# indsensor2.net
KiCad netlist of a schematic drawn in EAGLE
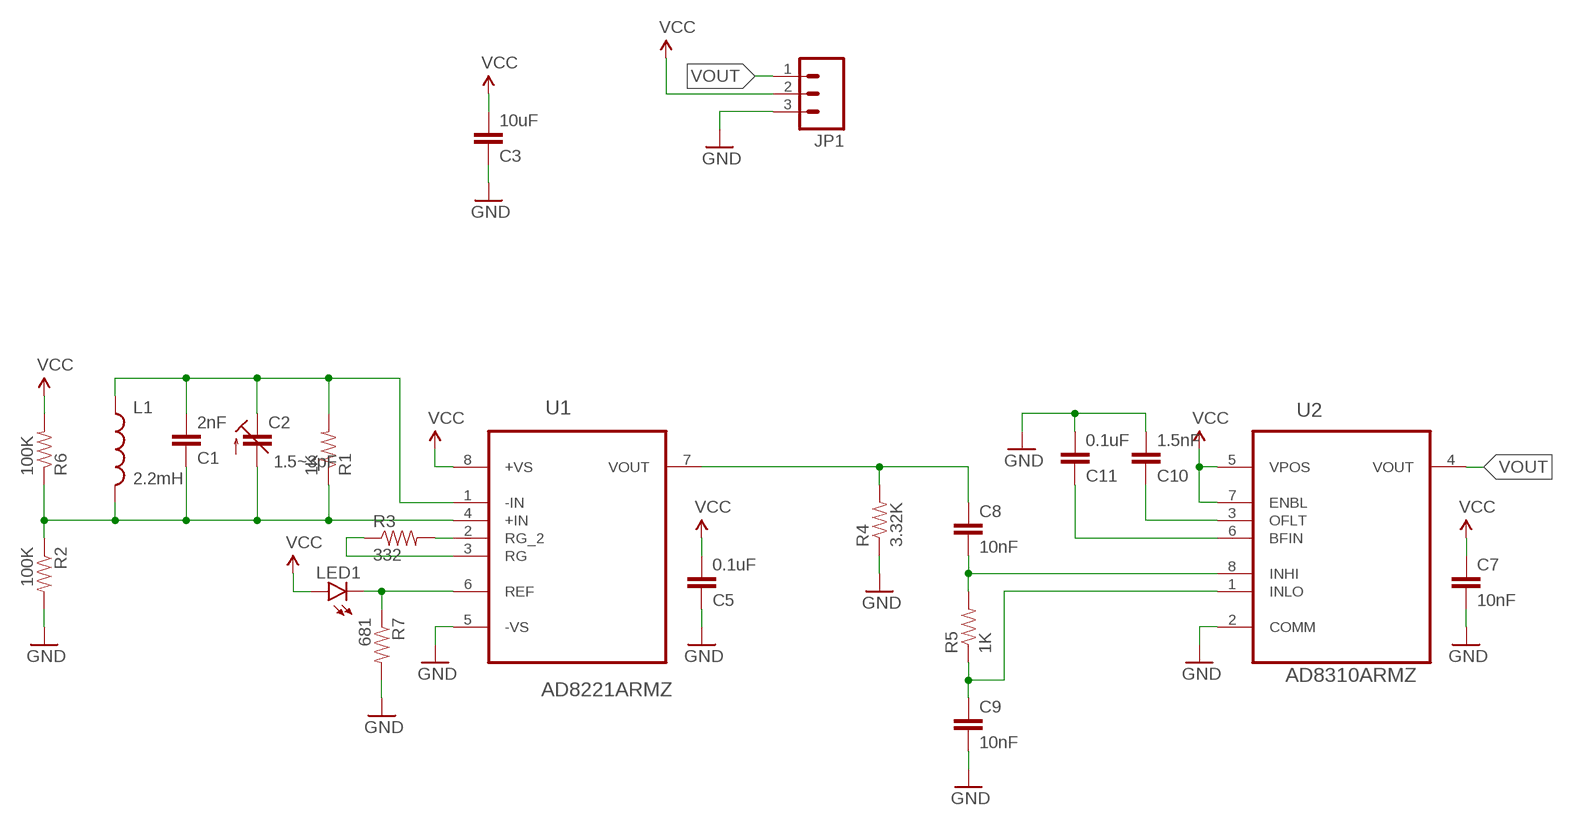
[diagram p0: schematic, sheet 1]

(export (version "E")
  (design (tool "Eeschema 10.0.6"))
  (components
    (comp (ref "C1")
      (value "2nF")
      (footprint "eagle-import:0603-CAP")
      (libsource (lib "eagle-import") (part "CAP0603-CAP"))
    )
    (comp (ref "C2")
      (value "1.5~3pF")
      (footprint "eagle-import:TRIMCAP-TZY")
      (libsource (lib "eagle-import") (part "TRIMCAP-TZY"))
    )
    (comp (ref "C3")
      (value "10uF")
      (footprint "eagle-import:0603-CAP")
      (libsource (lib "eagle-import") (part "CAP0603-CAP"))
    )
    (comp (ref "C5")
      (value "0.1uF")
      (footprint "eagle-import:0603-CAP")
      (libsource (lib "eagle-import") (part "CAP0603-CAP"))
    )
    (comp (ref "C7")
      (value "10nF")
      (footprint "eagle-import:0603-CAP")
      (libsource (lib "eagle-import") (part "CAP0603-CAP"))
    )
    (comp (ref "C8")
      (value "10nF")
      (footprint "eagle-import:0603-CAP")
      (libsource (lib "eagle-import") (part "CAP0603-CAP"))
    )
    (comp (ref "C9")
      (value "10nF")
      (footprint "eagle-import:0603-CAP")
      (libsource (lib "eagle-import") (part "CAP0603-CAP"))
    )
    (comp (ref "C10")
      (value "1.5nF")
      (footprint "eagle-import:0603-CAP")
      (libsource (lib "eagle-import") (part "CAP0603-CAP"))
    )
    (comp (ref "C11")
      (value "0.1uF")
      (footprint "eagle-import:0603-CAP")
      (libsource (lib "eagle-import") (part "CAP0603-CAP"))
    )
    (comp (ref "JP1")
      (value "M03LOCK")
      (footprint "eagle-import:1X03_LOCK")
      (libsource (lib "eagle-import") (part "M03LOCK"))
    )
    (comp (ref "L1")
      (value "2.2mH")
      (footprint "eagle-import:1812")
      (libsource (lib "eagle-import") (part "LQH43N"))
    )
    (comp (ref "LED1")
      (value "LED0603")
      (footprint "eagle-import:LED-0603")
      (libsource (lib "eagle-import") (part "LED0603"))
    )
    (comp (ref "R1")
      (value "1K")
      (footprint "eagle-import:0603-RES")
      (libsource (lib "eagle-import") (part "RESISTOR0603"))
    )
    (comp (ref "R2")
      (value "100K")
      (footprint "eagle-import:0603-RES")
      (libsource (lib "eagle-import") (part "RESISTOR0603"))
    )
    (comp (ref "R3")
      (value "332")
      (footprint "eagle-import:0603-RES")
      (libsource (lib "eagle-import") (part "RESISTOR0603"))
    )
    (comp (ref "R4")
      (value "3.32K")
      (footprint "eagle-import:0603-RES")
      (libsource (lib "eagle-import") (part "RESISTOR0603"))
    )
    (comp (ref "R5")
      (value "1K")
      (footprint "eagle-import:0603-RES")
      (libsource (lib "eagle-import") (part "RESISTOR0603"))
    )
    (comp (ref "R6")
      (value "100K")
      (footprint "eagle-import:0603-RES")
      (libsource (lib "eagle-import") (part "RESISTOR0603"))
    )
    (comp (ref "R7")
      (value "681")
      (footprint "eagle-import:0603-RES")
      (libsource (lib "eagle-import") (part "RESISTOR0603"))
    )
    (comp (ref "U1")
      (value "AD8221ARMZ")
      (footprint "eagle-import:SOP65P490X110-8N")
      (libsource (lib "eagle-import") (part "AD8221ARMZ"))
    )
    (comp (ref "U2")
      (value "AD8310ARMZ")
      (footprint "eagle-import:SOP65P490X110-8N")
      (libsource (lib "eagle-import") (part "AD8310ARMZ"))
    )
  )
  (nets
    (net (code "1") (name "GND") (class "Default")
      (node (ref "C10") (pin "2") (pinfunction "2_2") (pintype "passive"))
      (node (ref "C11") (pin "2") (pinfunction "2_2") (pintype "passive"))
      (node (ref "C3") (pin "1") (pinfunction "1_1") (pintype "passive"))
      (node (ref "C5") (pin "1") (pinfunction "1_1") (pintype "passive"))
      (node (ref "C7") (pin "2") (pinfunction "2_2") (pintype "passive"))
      (node (ref "C9") (pin "2") (pinfunction "2_2") (pintype "passive"))
      (node (ref "JP1") (pin "3") (pinfunction "3_3") (pintype "passive"))
      (node (ref "R2") (pin "2") (pinfunction "2_2") (pintype "passive"))
      (node (ref "R4") (pin "1") (pinfunction "1_1") (pintype "passive"))
      (node (ref "R7") (pin "2") (pinfunction "2_2") (pintype "passive"))
      (node (ref "U1") (pin "5") (pinfunction "-VS_5") (pintype "power_in"))
      (node (ref "U2") (pin "2") (pinfunction "COMM_2") (pintype "passive"))
    )
    (net (code "2") (name "Net-(C2-A)") (class "Default")
      (node (ref "C1") (pin "1") (pinfunction "1_1") (pintype "passive"))
      (node (ref "C2") (pin "1") (pinfunction "A_1") (pintype "passive"))
      (node (ref "L1") (pin "2") (pinfunction "2_2") (pintype "passive"))
      (node (ref "R1") (pin "1") (pinfunction "1_1") (pintype "passive"))
      (node (ref "R2") (pin "1") (pinfunction "1_1") (pintype "passive"))
      (node (ref "R6") (pin "1") (pinfunction "1_1") (pintype "passive"))
      (node (ref "U1") (pin "4") (pinfunction "+IN_4") (pintype "input"))
    )
    (net (code "3") (name "Net-(C2-E)") (class "Default")
      (node (ref "C1") (pin "2") (pinfunction "2_2") (pintype "passive"))
      (node (ref "C2") (pin "2") (pinfunction "E_2") (pintype "passive"))
      (node (ref "L1") (pin "1") (pinfunction "1_1") (pintype "passive"))
      (node (ref "R1") (pin "2") (pinfunction "2_2") (pintype "passive"))
      (node (ref "U1") (pin "1") (pinfunction "-IN_1") (pintype "input"))
    )
    (net (code "4") (name "Net-(U1-REF)") (class "Default")
      (node (ref "LED1") (pin "C") (pinfunction "C_C") (pintype "passive"))
      (node (ref "R7") (pin "1") (pinfunction "1_1") (pintype "passive"))
      (node (ref "U1") (pin "6") (pinfunction "REF_6") (pintype "passive"))
    )
    (net (code "5") (name "Net-(U1-RG)") (class "Default")
      (node (ref "R3") (pin "1") (pinfunction "1_1") (pintype "passive"))
      (node (ref "U1") (pin "3") (pinfunction "RG_3") (pintype "input"))
    )
    (net (code "6") (name "Net-(U1-RG_2)") (class "Default")
      (node (ref "R3") (pin "2") (pinfunction "2_2") (pintype "passive"))
      (node (ref "U1") (pin "2") (pinfunction "RG_2_2") (pintype "input"))
    )
    (net (code "7") (name "Net-(U1-VOUT)") (class "Default")
      (node (ref "C8") (pin "1") (pinfunction "1_1") (pintype "passive"))
      (node (ref "R4") (pin "2") (pinfunction "2_2") (pintype "passive"))
      (node (ref "U1") (pin "7") (pinfunction "VOUT_7") (pintype "output"))
    )
    (net (code "8") (name "Net-(U2-BFIN)") (class "Default")
      (node (ref "C11") (pin "1") (pinfunction "1_1") (pintype "passive"))
      (node (ref "U2") (pin "6") (pinfunction "BFIN_6") (pintype "input"))
    )
    (net (code "9") (name "Net-(U2-INHI)") (class "Default")
      (node (ref "C8") (pin "2") (pinfunction "2_2") (pintype "passive"))
      (node (ref "R5") (pin "2") (pinfunction "2_2") (pintype "passive"))
      (node (ref "U2") (pin "8") (pinfunction "INHI_8") (pintype "input"))
    )
    (net (code "10") (name "Net-(U2-INLO)") (class "Default")
      (node (ref "C9") (pin "1") (pinfunction "1_1") (pintype "passive"))
      (node (ref "R5") (pin "1") (pinfunction "1_1") (pintype "passive"))
      (node (ref "U2") (pin "1") (pinfunction "INLO_1") (pintype "input"))
    )
    (net (code "11") (name "Net-(U2-OFLT)") (class "Default")
      (node (ref "C10") (pin "1") (pinfunction "1_1") (pintype "passive"))
      (node (ref "U2") (pin "3") (pinfunction "OFLT_3") (pintype "passive"))
    )
    (net (code "12") (name "VCC") (class "Default")
      (node (ref "C3") (pin "2") (pinfunction "2_2") (pintype "passive"))
      (node (ref "C5") (pin "2") (pinfunction "2_2") (pintype "passive"))
      (node (ref "C7") (pin "1") (pinfunction "1_1") (pintype "passive"))
      (node (ref "JP1") (pin "2") (pinfunction "2_2") (pintype "passive"))
      (node (ref "LED1") (pin "A") (pinfunction "A_A") (pintype "passive"))
      (node (ref "R6") (pin "2") (pinfunction "2_2") (pintype "passive"))
      (node (ref "U1") (pin "8") (pinfunction "+VS_8") (pintype "power_in"))
      (node (ref "U2") (pin "5") (pinfunction "VPOS_5") (pintype "power_in"))
      (node (ref "U2") (pin "7") (pinfunction "ENBL_7") (pintype "input"))
    )
    (net (code "13") (name "VOUT") (class "Default")
      (node (ref "JP1") (pin "1") (pinfunction "1_1") (pintype "passive"))
      (node (ref "U2") (pin "4") (pinfunction "VOUT_4") (pintype "output"))
    )
  )
)
